# Battery_Heating_System.net
KiCad netlist of a schematic drawn in Altium Designer
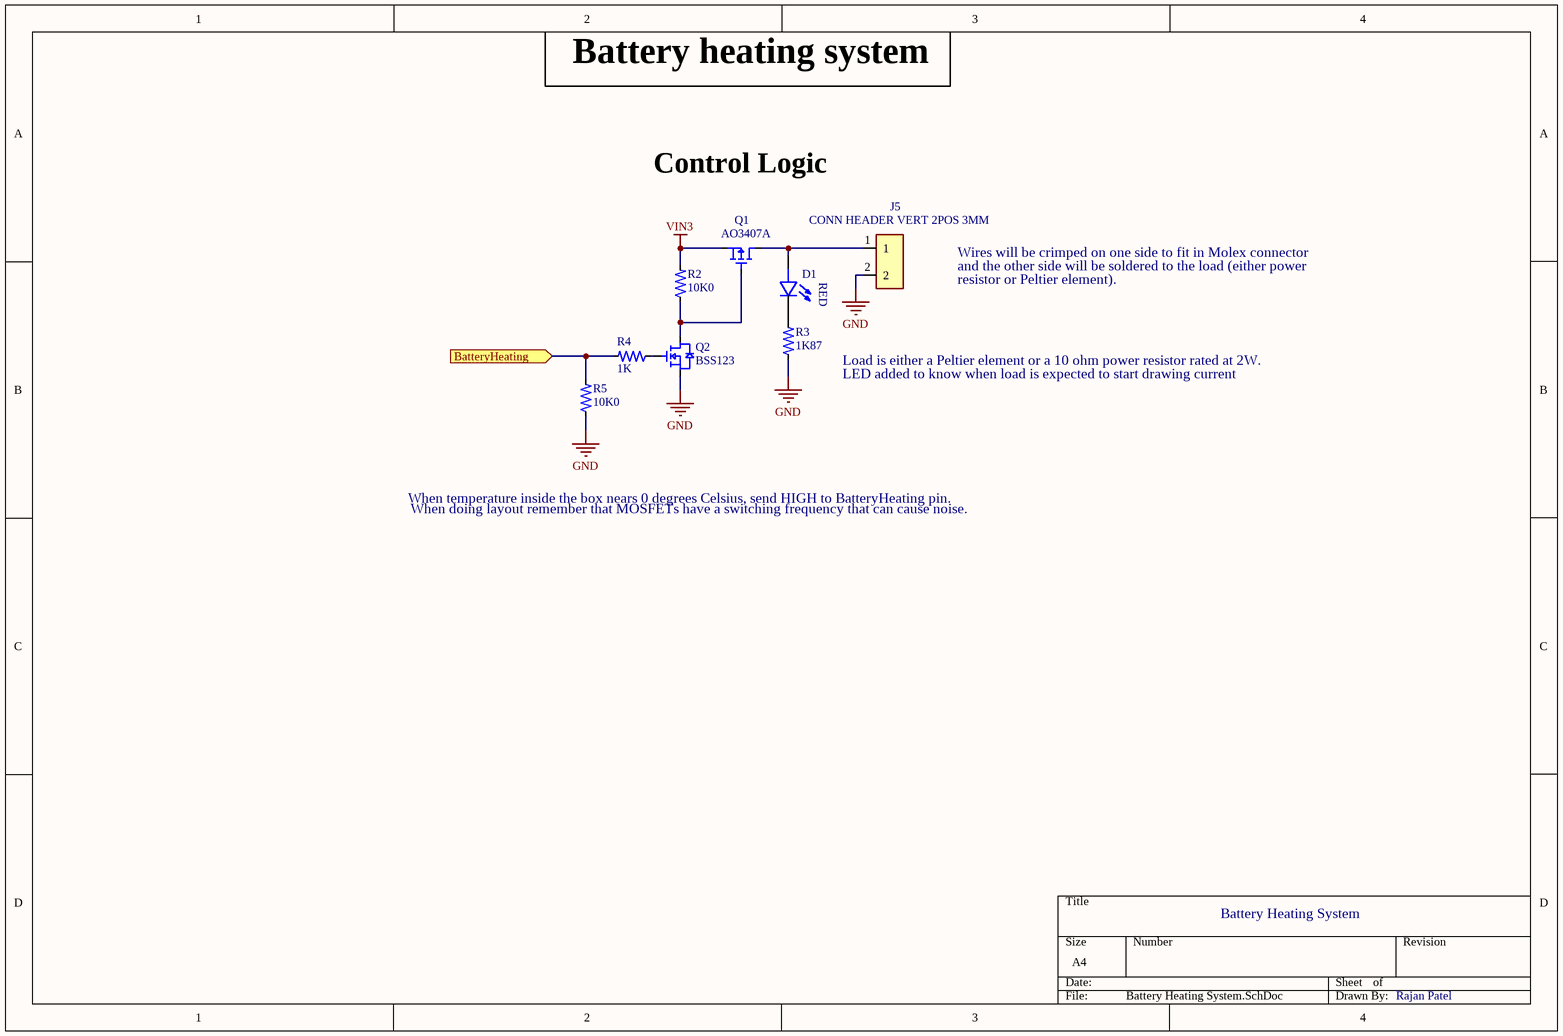
[diagram p0: Battery Heating System.SchDoc]

(export (version "E")
  (design (tool "Eeschema 10.0.6"))
  (components
    (comp (ref "D1")
      (value "LED 0805")
      (footprint "LED_0805")
      (description "Red LED Indication - Discrete 1.7V 0805 (2012 Metric)")
      (fields (field (name "MP") "7012X1"))
      (libsource (lib "Payload schlib") (part "LED 0805"))
    )
    (comp (ref "J5")
      (value "CONN HEADER VERT 2POS 3MM")
      (footprint "CONN HEADER VERT 2POS 3MM")
      (description "Rectangular Power Connector, 2 Contact(s), Female, Solder Terminal")
      (fields (field (name "MF") "Molex") (field (name "MP") "0436500200"))
      (libsource (lib "Payload schlib") (part "0436500228"))
    )
    (comp (ref "Q1")
      (value "AO3407A")
      (footprint "AO3407A")
      (fields (field (name "MANUFACTURER") "Alpha & Omega Semiconductor"))
      (libsource (lib "Payload schlib") (part "AO3407A"))
    )
    (comp (ref "Q2")
      (value "BSS123")
      (footprint "BSS123")
      (fields (field (name "MANUFACTURER") "ON Semiconductor / Fairchild"))
      (libsource (lib "Payload schlib") (part "BSS123_1"))
    )
    (comp (ref "R2")
      (value "10K0")
      (footprint "res 0805")
      (fields
        (field (name "MP") "2-2176053-2")
        (field (name "MF") "TE Connectivity")
        (field (name "TOLERANCE") "1%")
      )
      (libsource (lib "Payload schlib") (part "Resistor 0805"))
    )
    (comp (ref "R3")
      (value "1K87")
      (footprint "res 0805")
      (fields
        (field (name "MP") "2-2176053-2")
        (field (name "MF") "TE Connectivity")
        (field (name "TOLERANCE") "1%")
      )
      (libsource (lib "Payload schlib") (part "Resistor 0805"))
    )
    (comp (ref "R4")
      (value "1K")
      (footprint "res 0805")
      (fields
        (field (name "MP") "2-2176053-2")
        (field (name "MF") "TE Connectivity")
        (field (name "TOLERANCE") "1%")
      )
      (libsource (lib "Payload schlib") (part "Resistor 0805"))
    )
    (comp (ref "R5")
      (value "10K0")
      (footprint "res 0805")
      (fields
        (field (name "MP") "2-2176053-2")
        (field (name "MF") "TE Connectivity")
        (field (name "TOLERANCE") "1%")
      )
      (libsource (lib "Payload schlib") (part "Resistor 0805"))
    )
  )
  (nets
    (net (code "1") (name "/BatteryHeating") (class "Default")
      (node (ref "R4") (pin "2") (pinfunction "2_2") (pintype "passive"))
      (node (ref "R5") (pin "2") (pinfunction "2_2") (pintype "passive"))
    )
    (net (code "2") (name "GND") (class "Default")
      (node (ref "J5") (pin "2") (pinfunction "2_2") (pintype "passive"))
      (node (ref "Q2") (pin "2") (pinfunction "Source_2") (pintype "passive"))
      (node (ref "R3") (pin "1") (pinfunction "1_1") (pintype "passive"))
      (node (ref "R5") (pin "1") (pinfunction "1_1") (pintype "passive"))
    )
    (net (code "3") (name "Net-(D1-A)") (class "Default")
      (node (ref "D1") (pin "2") (pinfunction "A_2") (pintype "passive"))
      (node (ref "J5") (pin "1") (pinfunction "1_1") (pintype "passive"))
      (node (ref "Q1") (pin "3") (pinfunction "Drain_3") (pintype "passive"))
    )
    (net (code "4") (name "Net-(D1-C)") (class "Default")
      (node (ref "D1") (pin "1") (pinfunction "C_1") (pintype "passive"))
      (node (ref "R3") (pin "2") (pinfunction "2_2") (pintype "passive"))
    )
    (net (code "5") (name "Net-(Q1-Gate)") (class "Default")
      (node (ref "Q1") (pin "1") (pinfunction "Gate_1") (pintype "passive"))
      (node (ref "Q2") (pin "3") (pinfunction "Drain_3") (pintype "passive"))
      (node (ref "R2") (pin "1") (pinfunction "1_1") (pintype "passive"))
    )
    (net (code "6") (name "Net-(Q2-Gate)") (class "Default")
      (node (ref "Q2") (pin "1") (pinfunction "Gate_1") (pintype "passive"))
      (node (ref "R4") (pin "1") (pinfunction "1_1") (pintype "passive"))
    )
    (net (code "7") (name "VIN3") (class "Default")
      (node (ref "Q1") (pin "2") (pinfunction "Source_2") (pintype "passive"))
      (node (ref "R2") (pin "2") (pinfunction "2_2") (pintype "passive"))
    )
  )
)
